# PIDController.net
KiCad netlist of a schematic drawn in EAGLE
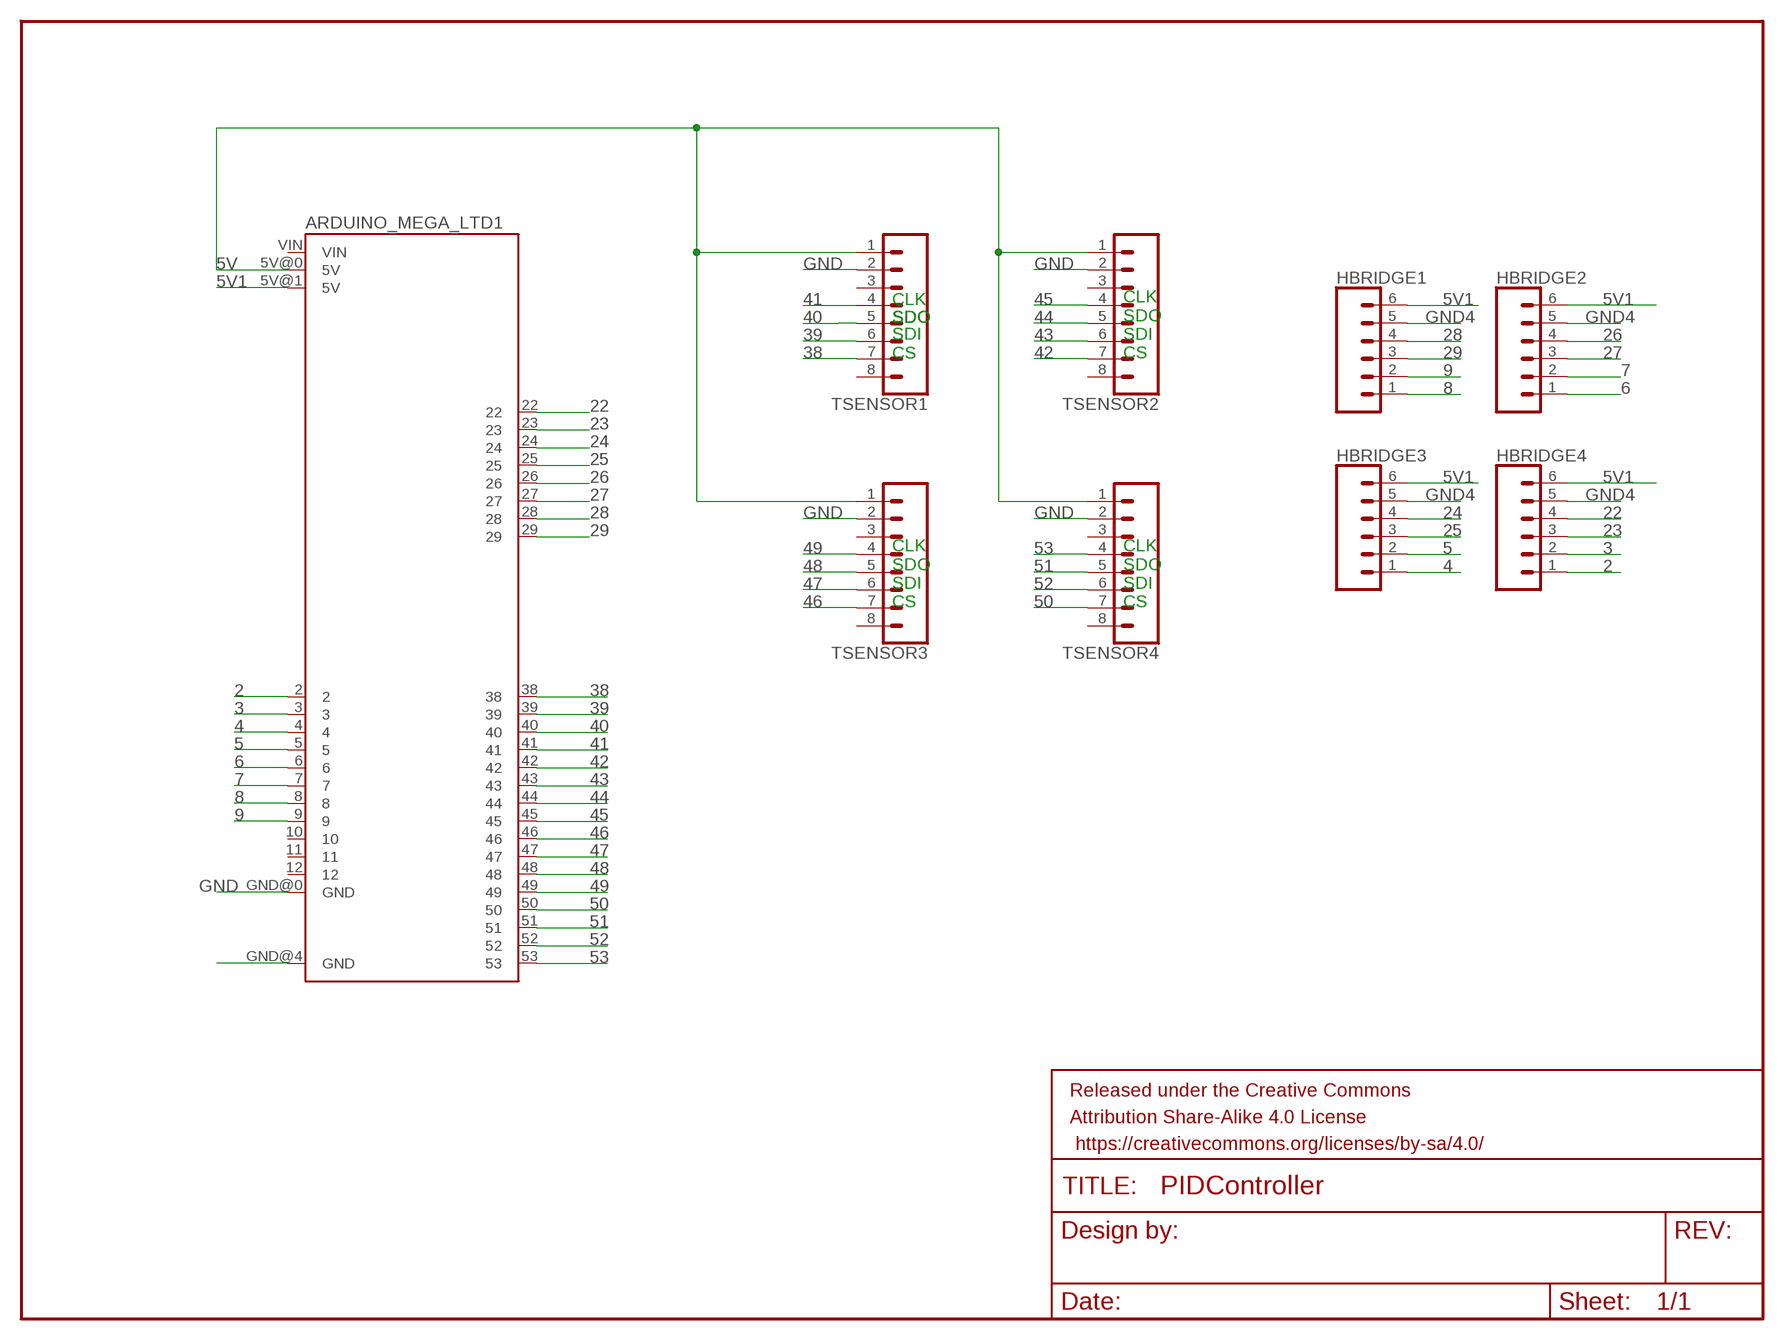
[diagram p0: schematic, sheet 1]

(export (version "E")
  (design (tool "Eeschema 10.0.6"))
  (components
    (comp (ref "ARDUINO_MEGA_LTD1")
      (value "ARDUINO_MEGA_LTD")
      (footprint "eagle-import:ARDUINO_MEGA_LTD")
      (libsource (lib "eagle-import") (part "ARDUINO_MEGA_LTD"))
    )
    (comp (ref "FRAME2")
      (value "FRAME-LETTERNO_PACKAGE")
      (footprint "eagle-import:DUMMY")
      (fields (field (name "DESIGNER") "Jamilla Akhund-Zade, de Bivort Lab"))
      (libsource (lib "eagle-import") (part "FRAME-LETTERNO_PACKAGE"))
    )
    (comp (ref "HBRIDGE1")
      (value "CONN_06LONGPADS")
      (footprint "eagle-import:1X06_LONGPADS")
      (libsource (lib "eagle-import") (part "CONN_06LONGPADS"))
    )
    (comp (ref "HBRIDGE2")
      (value "CONN_06LONGPADS")
      (footprint "eagle-import:1X06_LONGPADS")
      (libsource (lib "eagle-import") (part "CONN_06LONGPADS"))
    )
    (comp (ref "HBRIDGE3")
      (value "CONN_06LONGPADS")
      (footprint "eagle-import:1X06_LONGPADS")
      (libsource (lib "eagle-import") (part "CONN_06LONGPADS"))
    )
    (comp (ref "HBRIDGE4")
      (value "CONN_06LONGPADS")
      (footprint "eagle-import:1X06_LONGPADS")
      (libsource (lib "eagle-import") (part "CONN_06LONGPADS"))
    )
    (comp (ref "TSENSOR1")
      (value "CONN_08\"")
      (footprint "eagle-import:1X08")
      (libsource (lib "eagle-import") (part "CONN_08{dblquote}"))
    )
    (comp (ref "TSENSOR2")
      (value "CONN_08\"")
      (footprint "eagle-import:1X08")
      (libsource (lib "eagle-import") (part "CONN_08{dblquote}"))
    )
    (comp (ref "TSENSOR3")
      (value "CONN_08\"")
      (footprint "eagle-import:1X08")
      (libsource (lib "eagle-import") (part "CONN_08{dblquote}"))
    )
    (comp (ref "TSENSOR4")
      (value "CONN_08\"")
      (footprint "eagle-import:1X08")
      (libsource (lib "eagle-import") (part "CONN_08{dblquote}"))
    )
  )
  (nets
    (net (code "1") (name "/2") (class "Default")
      (node (ref "ARDUINO_MEGA_LTD1") (pin "2") (pinfunction "2_2") (pintype "bidirectional"))
      (node (ref "HBRIDGE4") (pin "1") (pinfunction "1_1") (pintype "passive"))
    )
    (net (code "2") (name "/3") (class "Default")
      (node (ref "ARDUINO_MEGA_LTD1") (pin "3") (pinfunction "3_3") (pintype "bidirectional"))
      (node (ref "HBRIDGE4") (pin "2") (pinfunction "2_2") (pintype "passive"))
    )
    (net (code "3") (name "/4") (class "Default")
      (node (ref "ARDUINO_MEGA_LTD1") (pin "4") (pinfunction "4_4") (pintype "bidirectional"))
      (node (ref "HBRIDGE3") (pin "1") (pinfunction "1_1") (pintype "passive"))
    )
    (net (code "4") (name "/5") (class "Default")
      (node (ref "ARDUINO_MEGA_LTD1") (pin "5") (pinfunction "5_5") (pintype "bidirectional"))
      (node (ref "HBRIDGE3") (pin "2") (pinfunction "2_2") (pintype "passive"))
    )
    (net (code "5") (name "/5V") (class "Default")
      (node (ref "ARDUINO_MEGA_LTD1") (pin "5V@0") (pinfunction "5V_5V@0") (pintype "bidirectional"))
      (node (ref "TSENSOR1") (pin "1") (pinfunction "1_1") (pintype "passive"))
      (node (ref "TSENSOR2") (pin "1") (pinfunction "1_1") (pintype "passive"))
      (node (ref "TSENSOR3") (pin "1") (pinfunction "1_1") (pintype "passive"))
      (node (ref "TSENSOR4") (pin "1") (pinfunction "1_1") (pintype "passive"))
    )
    (net (code "6") (name "/5V1") (class "Default")
      (node (ref "ARDUINO_MEGA_LTD1") (pin "5V@1") (pinfunction "5V_5V@1") (pintype "bidirectional"))
      (node (ref "HBRIDGE1") (pin "6") (pinfunction "6_6") (pintype "passive"))
      (node (ref "HBRIDGE2") (pin "6") (pinfunction "6_6") (pintype "passive"))
      (node (ref "HBRIDGE3") (pin "6") (pinfunction "6_6") (pintype "passive"))
      (node (ref "HBRIDGE4") (pin "6") (pinfunction "6_6") (pintype "passive"))
    )
    (net (code "7") (name "/6") (class "Default")
      (node (ref "ARDUINO_MEGA_LTD1") (pin "6") (pinfunction "6_6") (pintype "bidirectional"))
      (node (ref "HBRIDGE2") (pin "1") (pinfunction "1_1") (pintype "passive"))
    )
    (net (code "8") (name "/7") (class "Default")
      (node (ref "ARDUINO_MEGA_LTD1") (pin "7") (pinfunction "7_7") (pintype "bidirectional"))
      (node (ref "HBRIDGE2") (pin "2") (pinfunction "2_2") (pintype "passive"))
    )
    (net (code "9") (name "/8") (class "Default")
      (node (ref "ARDUINO_MEGA_LTD1") (pin "8") (pinfunction "8_8") (pintype "bidirectional"))
      (node (ref "HBRIDGE1") (pin "1") (pinfunction "1_1") (pintype "passive"))
    )
    (net (code "10") (name "/9") (class "Default")
      (node (ref "ARDUINO_MEGA_LTD1") (pin "9") (pinfunction "9_9") (pintype "bidirectional"))
      (node (ref "HBRIDGE1") (pin "2") (pinfunction "2_2") (pintype "passive"))
    )
    (net (code "11") (name "/22") (class "Default")
      (node (ref "ARDUINO_MEGA_LTD1") (pin "22") (pinfunction "22_22") (pintype "bidirectional"))
      (node (ref "HBRIDGE4") (pin "4") (pinfunction "4_4") (pintype "passive"))
    )
    (net (code "12") (name "/23") (class "Default")
      (node (ref "ARDUINO_MEGA_LTD1") (pin "23") (pinfunction "23_23") (pintype "bidirectional"))
      (node (ref "HBRIDGE4") (pin "3") (pinfunction "3_3") (pintype "passive"))
    )
    (net (code "13") (name "/24") (class "Default")
      (node (ref "ARDUINO_MEGA_LTD1") (pin "24") (pinfunction "24_24") (pintype "bidirectional"))
      (node (ref "HBRIDGE3") (pin "4") (pinfunction "4_4") (pintype "passive"))
    )
    (net (code "14") (name "/25") (class "Default")
      (node (ref "ARDUINO_MEGA_LTD1") (pin "25") (pinfunction "25_25") (pintype "bidirectional"))
      (node (ref "HBRIDGE3") (pin "3") (pinfunction "3_3") (pintype "passive"))
    )
    (net (code "15") (name "/26") (class "Default")
      (node (ref "ARDUINO_MEGA_LTD1") (pin "26") (pinfunction "26_26") (pintype "bidirectional"))
      (node (ref "HBRIDGE2") (pin "4") (pinfunction "4_4") (pintype "passive"))
    )
    (net (code "16") (name "/27") (class "Default")
      (node (ref "ARDUINO_MEGA_LTD1") (pin "27") (pinfunction "27_27") (pintype "bidirectional"))
      (node (ref "HBRIDGE2") (pin "3") (pinfunction "3_3") (pintype "passive"))
    )
    (net (code "17") (name "/28") (class "Default")
      (node (ref "ARDUINO_MEGA_LTD1") (pin "28") (pinfunction "28_28") (pintype "bidirectional"))
      (node (ref "HBRIDGE1") (pin "4") (pinfunction "4_4") (pintype "passive"))
    )
    (net (code "18") (name "/29") (class "Default")
      (node (ref "ARDUINO_MEGA_LTD1") (pin "29") (pinfunction "29_29") (pintype "bidirectional"))
      (node (ref "HBRIDGE1") (pin "3") (pinfunction "3_3") (pintype "passive"))
    )
    (net (code "19") (name "/38") (class "Default")
      (node (ref "ARDUINO_MEGA_LTD1") (pin "38") (pinfunction "38_38") (pintype "bidirectional"))
      (node (ref "TSENSOR1") (pin "7") (pinfunction "7_7") (pintype "passive"))
    )
    (net (code "20") (name "/39") (class "Default")
      (node (ref "ARDUINO_MEGA_LTD1") (pin "39") (pinfunction "39_39") (pintype "bidirectional"))
      (node (ref "TSENSOR1") (pin "6") (pinfunction "6_6") (pintype "passive"))
    )
    (net (code "21") (name "/40") (class "Default")
      (node (ref "ARDUINO_MEGA_LTD1") (pin "40") (pinfunction "40_40") (pintype "bidirectional"))
      (node (ref "TSENSOR1") (pin "5") (pinfunction "5_5") (pintype "passive"))
    )
    (net (code "22") (name "/41") (class "Default")
      (node (ref "ARDUINO_MEGA_LTD1") (pin "41") (pinfunction "41_41") (pintype "bidirectional"))
      (node (ref "TSENSOR1") (pin "4") (pinfunction "4_4") (pintype "passive"))
    )
    (net (code "23") (name "/42") (class "Default")
      (node (ref "ARDUINO_MEGA_LTD1") (pin "42") (pinfunction "42_42") (pintype "bidirectional"))
      (node (ref "TSENSOR2") (pin "7") (pinfunction "7_7") (pintype "passive"))
    )
    (net (code "24") (name "/43") (class "Default")
      (node (ref "ARDUINO_MEGA_LTD1") (pin "43") (pinfunction "43_43") (pintype "bidirectional"))
      (node (ref "TSENSOR2") (pin "6") (pinfunction "6_6") (pintype "passive"))
    )
    (net (code "25") (name "/44") (class "Default")
      (node (ref "ARDUINO_MEGA_LTD1") (pin "44") (pinfunction "44_44") (pintype "bidirectional"))
      (node (ref "TSENSOR2") (pin "5") (pinfunction "5_5") (pintype "passive"))
    )
    (net (code "26") (name "/45") (class "Default")
      (node (ref "ARDUINO_MEGA_LTD1") (pin "45") (pinfunction "45_45") (pintype "bidirectional"))
      (node (ref "TSENSOR2") (pin "4") (pinfunction "4_4") (pintype "passive"))
    )
    (net (code "27") (name "/46") (class "Default")
      (node (ref "ARDUINO_MEGA_LTD1") (pin "46") (pinfunction "46_46") (pintype "bidirectional"))
      (node (ref "TSENSOR3") (pin "7") (pinfunction "7_7") (pintype "passive"))
    )
    (net (code "28") (name "/47") (class "Default")
      (node (ref "ARDUINO_MEGA_LTD1") (pin "47") (pinfunction "47_47") (pintype "bidirectional"))
      (node (ref "TSENSOR3") (pin "6") (pinfunction "6_6") (pintype "passive"))
    )
    (net (code "29") (name "/48") (class "Default")
      (node (ref "ARDUINO_MEGA_LTD1") (pin "48") (pinfunction "48_48") (pintype "bidirectional"))
      (node (ref "TSENSOR3") (pin "5") (pinfunction "5_5") (pintype "passive"))
    )
    (net (code "30") (name "/49") (class "Default")
      (node (ref "ARDUINO_MEGA_LTD1") (pin "49") (pinfunction "49_49") (pintype "bidirectional"))
      (node (ref "TSENSOR3") (pin "4") (pinfunction "4_4") (pintype "passive"))
    )
    (net (code "31") (name "/50") (class "Default")
      (node (ref "ARDUINO_MEGA_LTD1") (pin "50") (pinfunction "50_50") (pintype "bidirectional"))
      (node (ref "TSENSOR4") (pin "7") (pinfunction "7_7") (pintype "passive"))
    )
    (net (code "32") (name "/51") (class "Default")
      (node (ref "ARDUINO_MEGA_LTD1") (pin "51") (pinfunction "51_51") (pintype "bidirectional"))
      (node (ref "TSENSOR4") (pin "5") (pinfunction "5_5") (pintype "passive"))
    )
    (net (code "33") (name "/52") (class "Default")
      (node (ref "ARDUINO_MEGA_LTD1") (pin "52") (pinfunction "52_52") (pintype "bidirectional"))
      (node (ref "TSENSOR4") (pin "6") (pinfunction "6_6") (pintype "passive"))
    )
    (net (code "34") (name "/53") (class "Default")
      (node (ref "ARDUINO_MEGA_LTD1") (pin "53") (pinfunction "53_53") (pintype "bidirectional"))
      (node (ref "TSENSOR4") (pin "4") (pinfunction "4_4") (pintype "passive"))
    )
    (net (code "35") (name "/GND") (class "Default")
      (node (ref "ARDUINO_MEGA_LTD1") (pin "GND@0") (pinfunction "GND_GND@0") (pintype "bidirectional"))
      (node (ref "TSENSOR1") (pin "2") (pinfunction "2_2") (pintype "passive"))
      (node (ref "TSENSOR2") (pin "2") (pinfunction "2_2") (pintype "passive"))
      (node (ref "TSENSOR3") (pin "2") (pinfunction "2_2") (pintype "passive"))
      (node (ref "TSENSOR4") (pin "2") (pinfunction "2_2") (pintype "passive"))
    )
    (net (code "36") (name "/GND4") (class "Default")
      (node (ref "ARDUINO_MEGA_LTD1") (pin "GND@4") (pinfunction "GND_GND@4") (pintype "bidirectional"))
      (node (ref "HBRIDGE1") (pin "5") (pinfunction "5_5") (pintype "passive"))
      (node (ref "HBRIDGE2") (pin "5") (pinfunction "5_5") (pintype "passive"))
      (node (ref "HBRIDGE3") (pin "5") (pinfunction "5_5") (pintype "passive"))
      (node (ref "HBRIDGE4") (pin "5") (pinfunction "5_5") (pintype "passive"))
    )
    (net (code "37") (name "unconnected-(ARDUINO_MEGA_LTD1-Pad10)") (class "Default")
      (node (ref "ARDUINO_MEGA_LTD1") (pin "10") (pinfunction "10_10") (pintype "bidirectional"))
    )
    (net (code "38") (name "unconnected-(ARDUINO_MEGA_LTD1-Pad11)") (class "Default")
      (node (ref "ARDUINO_MEGA_LTD1") (pin "11") (pinfunction "11_11") (pintype "bidirectional"))
    )
    (net (code "39") (name "unconnected-(ARDUINO_MEGA_LTD1-Pad12)") (class "Default")
      (node (ref "ARDUINO_MEGA_LTD1") (pin "12") (pinfunction "12_12") (pintype "bidirectional"))
    )
    (net (code "40") (name "unconnected-(ARDUINO_MEGA_LTD1-PadVIN)") (class "Default")
      (node (ref "ARDUINO_MEGA_LTD1") (pin "VIN") (pinfunction "VIN_VIN") (pintype "bidirectional"))
    )
    (net (code "41") (name "unconnected-(TSENSOR1-Pad3)") (class "Default")
      (node (ref "TSENSOR1") (pin "3") (pinfunction "3_3") (pintype "passive"))
    )
    (net (code "42") (name "unconnected-(TSENSOR1-Pad8)") (class "Default")
      (node (ref "TSENSOR1") (pin "8") (pinfunction "8_8") (pintype "passive"))
    )
    (net (code "43") (name "unconnected-(TSENSOR2-Pad3)") (class "Default")
      (node (ref "TSENSOR2") (pin "3") (pinfunction "3_3") (pintype "passive"))
    )
    (net (code "44") (name "unconnected-(TSENSOR2-Pad8)") (class "Default")
      (node (ref "TSENSOR2") (pin "8") (pinfunction "8_8") (pintype "passive"))
    )
    (net (code "45") (name "unconnected-(TSENSOR3-Pad3)") (class "Default")
      (node (ref "TSENSOR3") (pin "3") (pinfunction "3_3") (pintype "passive"))
    )
    (net (code "46") (name "unconnected-(TSENSOR3-Pad8)") (class "Default")
      (node (ref "TSENSOR3") (pin "8") (pinfunction "8_8") (pintype "passive"))
    )
    (net (code "47") (name "unconnected-(TSENSOR4-Pad3)") (class "Default")
      (node (ref "TSENSOR4") (pin "3") (pinfunction "3_3") (pintype "passive"))
    )
    (net (code "48") (name "unconnected-(TSENSOR4-Pad8)") (class "Default")
      (node (ref "TSENSOR4") (pin "8") (pinfunction "8_8") (pintype "passive"))
    )
  )
)
